# KSM.net
KiCad netlist of a schematic drawn in EAGLE
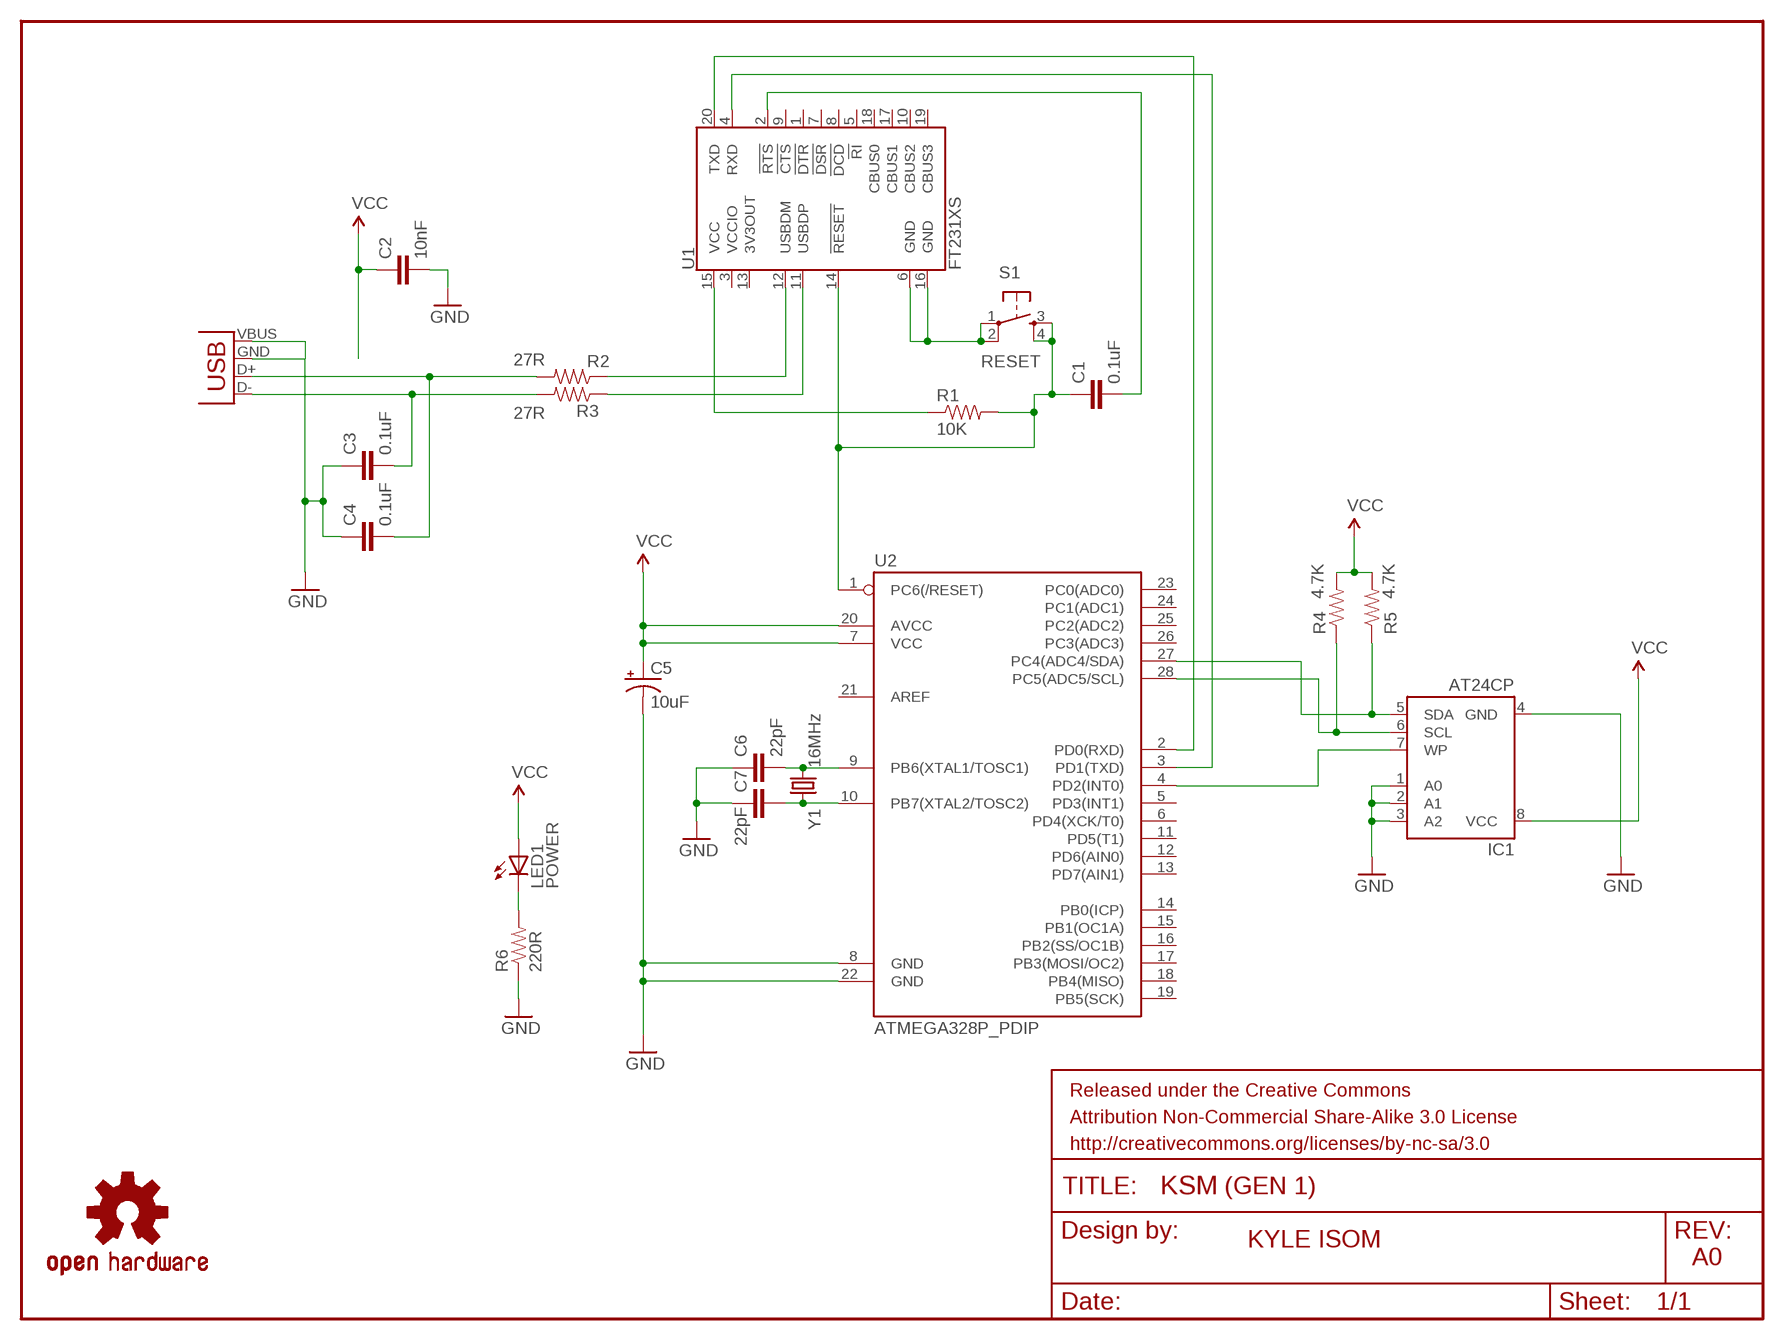
[diagram p0: schematic, sheet 1]

(export (version "E")
  (design (tool "Eeschema 10.0.6"))
  (components
    (comp (ref "C1")
      (value "0.1uF")
      (footprint "eagle-import:CAP-PTH-SMALL")
      (libsource (lib "eagle-import") (part "CAPPTH"))
    )
    (comp (ref "C2")
      (value "10nF")
      (footprint "eagle-import:CAP-PTH-SMALL")
      (libsource (lib "eagle-import") (part "CAPPTH"))
    )
    (comp (ref "C3")
      (value "0.1uF")
      (footprint "eagle-import:CAP-PTH-SMALL")
      (libsource (lib "eagle-import") (part "CAPPTH"))
    )
    (comp (ref "C4")
      (value "0.1uF")
      (footprint "eagle-import:CAP-PTH-SMALL")
      (libsource (lib "eagle-import") (part "CAPPTH"))
    )
    (comp (ref "C5")
      (value "10uF")
      (footprint "eagle-import:CPOL-RADIAL-10UF-25V")
      (libsource (lib "eagle-import") (part "CAP_POLPTH2"))
    )
    (comp (ref "C6")
      (value "22pF")
      (footprint "eagle-import:CAP-PTH-SMALL")
      (libsource (lib "eagle-import") (part "CAPPTH"))
    )
    (comp (ref "C7")
      (value "22pF")
      (footprint "eagle-import:CAP-PTH-SMALL")
      (libsource (lib "eagle-import") (part "CAPPTH"))
    )
    (comp (ref "FRAME1")
      (value "FRAME-LETTER")
      (footprint "eagle-import:CREATIVE_COMMONS")
      (libsource (lib "eagle-import") (part "FRAME-LETTER"))
    )
    (comp (ref "IC1")
      (value "AT24CP")
      (footprint "eagle-import:DIL08")
      (fields (field (name "MPN") "AT24C1024BW-SH-B"))
      (libsource (lib "eagle-import") (part "AT24CP"))
    )
    (comp (ref "JP1")
      (value "USB-A-H")
      (footprint "eagle-import:USB-A-H")
      (libsource (lib "eagle-import") (part "USB-A-H"))
    )
    (comp (ref "LED1")
      (value "POWER")
      (footprint "eagle-import:LED3MM")
      (libsource (lib "eagle-import") (part "LED3MM"))
    )
    (comp (ref "LOGO1")
      (value "OSHW-LOGOL")
      (footprint "eagle-import:OSHW-LOGO-L")
      (libsource (lib "eagle-import") (part "OSHW-LOGOL"))
    )
    (comp (ref "R1")
      (value "10K")
      (footprint "eagle-import:AXIAL-0.4")
      (libsource (lib "eagle-import") (part "RESISTORPTH-1/4W"))
    )
    (comp (ref "R2")
      (value "27R")
      (footprint "eagle-import:AXIAL-0.4")
      (libsource (lib "eagle-import") (part "RESISTORPTH-1/4W"))
    )
    (comp (ref "R3")
      (value "27R")
      (footprint "eagle-import:AXIAL-0.4")
      (libsource (lib "eagle-import") (part "RESISTORPTH-1/4W"))
    )
    (comp (ref "R4")
      (value "4.7K")
      (footprint "eagle-import:AXIAL-0.4")
      (libsource (lib "eagle-import") (part "RESISTORPTH-1/4W"))
    )
    (comp (ref "R5")
      (value "4.7K")
      (footprint "eagle-import:AXIAL-0.4")
      (libsource (lib "eagle-import") (part "RESISTORPTH-1/4W"))
    )
    (comp (ref "R6")
      (value "220R")
      (footprint "eagle-import:AXIAL-0.4")
      (libsource (lib "eagle-import") (part "RESISTORPTH-1/4W"))
    )
    (comp (ref "S1")
      (value "RESET")
      (footprint "eagle-import:TACTILE-PTH")
      (libsource (lib "eagle-import") (part "TAC_SWITCHPTH"))
    )
    (comp (ref "U1")
      (value "FT231XS")
      (footprint "eagle-import:SSOP20_L")
      (libsource (lib "eagle-import") (part "FT231XS"))
    )
    (comp (ref "U2")
      (value "ATMEGA328P_PDIP")
      (footprint "eagle-import:DIL28-3")
      (libsource (lib "eagle-import") (part "ATMEGA328P_PDIP"))
    )
    (comp (ref "Y1")
      (value "16MHz")
      (footprint "eagle-import:HC49US")
      (libsource (lib "eagle-import") (part "CRYSTALHC49US"))
    )
  )
  (nets
    (net (code "1") (name "GND") (class "Default")
      (node (ref "C2") (pin "2") (pinfunction "2_2") (pintype "passive"))
      (node (ref "C3") (pin "1") (pinfunction "1_1") (pintype "passive"))
      (node (ref "C4") (pin "1") (pinfunction "1_1") (pintype "passive"))
      (node (ref "C5") (pin "2") (pinfunction "-_2") (pintype "passive"))
      (node (ref "C6") (pin "1") (pinfunction "1_1") (pintype "passive"))
      (node (ref "C7") (pin "1") (pinfunction "1_1") (pintype "passive"))
      (node (ref "IC1") (pin "1") (pinfunction "A0_1") (pintype "input"))
      (node (ref "IC1") (pin "2") (pinfunction "A1_2") (pintype "input"))
      (node (ref "IC1") (pin "3") (pinfunction "A2_3") (pintype "input"))
      (node (ref "IC1") (pin "4") (pinfunction "GND_4") (pintype "power_in"))
      (node (ref "JP1") (pin "GND") (pinfunction "VBUS_GND") (pintype "bidirectional"))
      (node (ref "JP1") (pin "VBUS") (pinfunction "GND_VBUS") (pintype "bidirectional"))
      (node (ref "R6") (pin "P$1") (pinfunction "1_P$1") (pintype "passive"))
      (node (ref "U2") (pin "22") (pinfunction "GND_22") (pintype "bidirectional"))
      (node (ref "U2") (pin "8") (pinfunction "GND_8") (pintype "bidirectional"))
    )
    (net (code "2") (name "Net-(IC1-SCL)") (class "Default")
      (node (ref "IC1") (pin "6") (pinfunction "SCL_6") (pintype "bidirectional"))
      (node (ref "R4") (pin "P$1") (pinfunction "1_P$1") (pintype "passive"))
      (node (ref "U2") (pin "28") (pinfunction "PC5(ADC5/SCL)_28") (pintype "bidirectional"))
    )
    (net (code "3") (name "Net-(IC1-SDA)") (class "Default")
      (node (ref "IC1") (pin "5") (pinfunction "SDA_5") (pintype "bidirectional"))
      (node (ref "R5") (pin "P$1") (pinfunction "1_P$1") (pintype "passive"))
      (node (ref "U2") (pin "27") (pinfunction "PC4(ADC4/SDA)_27") (pintype "bidirectional"))
    )
    (net (code "4") (name "Net-(IC1-WP)") (class "Default")
      (node (ref "IC1") (pin "7") (pinfunction "WP_7") (pintype "input"))
      (node (ref "U2") (pin "4") (pinfunction "PD2(INT0)_4") (pintype "bidirectional"))
    )
    (net (code "5") (name "Net-(JP1-D+)") (class "Default")
      (node (ref "C3") (pin "2") (pinfunction "2_2") (pintype "passive"))
      (node (ref "JP1") (pin "D-") (pinfunction "D+_D-") (pintype "bidirectional"))
      (node (ref "R3") (pin "P$2") (pinfunction "2_P$2") (pintype "passive"))
    )
    (net (code "6") (name "Net-(JP1-D-)") (class "Default")
      (node (ref "C4") (pin "2") (pinfunction "2_2") (pintype "passive"))
      (node (ref "JP1") (pin "D+") (pinfunction "D-_D+") (pintype "bidirectional"))
      (node (ref "R2") (pin "P$2") (pinfunction "2_P$2") (pintype "passive"))
    )
    (net (code "7") (name "Net-(LED1-C)") (class "Default")
      (node (ref "LED1") (pin "K") (pinfunction "C_K") (pintype "passive"))
      (node (ref "R6") (pin "P$2") (pinfunction "2_P$2") (pintype "passive"))
    )
    (net (code "8") (name "Net-(R1-1)") (class "Default")
      (node (ref "R1") (pin "P$1") (pinfunction "1_P$1") (pintype "passive"))
      (node (ref "U1") (pin "15") (pinfunction "VCC_15") (pintype "bidirectional"))
    )
    (net (code "9") (name "Net-(R1-2)") (class "Default")
      (node (ref "C1") (pin "1") (pinfunction "1_1") (pintype "passive"))
      (node (ref "R1") (pin "P$2") (pinfunction "2_P$2") (pintype "passive"))
      (node (ref "S1") (pin "3") (pinfunction "3_3") (pintype "passive"))
      (node (ref "S1") (pin "4") (pinfunction "4_4") (pintype "passive"))
      (node (ref "U1") (pin "14") (pinfunction "~{RESET}_14") (pintype "bidirectional"))
      (node (ref "U2") (pin "1") (pinfunction "PC6(/RESET)_1") (pintype "bidirectional"))
    )
    (net (code "10") (name "Net-(R2-1)") (class "Default")
      (node (ref "R2") (pin "P$1") (pinfunction "1_P$1") (pintype "passive"))
      (node (ref "U1") (pin "12") (pinfunction "USBDM_12") (pintype "bidirectional"))
    )
    (net (code "11") (name "Net-(R3-1)") (class "Default")
      (node (ref "R3") (pin "P$1") (pinfunction "1_P$1") (pintype "passive"))
      (node (ref "U1") (pin "11") (pinfunction "USBDP_11") (pintype "bidirectional"))
    )
    (net (code "12") (name "Net-(S1-Pad1)") (class "Default")
      (node (ref "S1") (pin "1") (pinfunction "1_1") (pintype "passive"))
      (node (ref "S1") (pin "2") (pinfunction "2_2") (pintype "passive"))
      (node (ref "U1") (pin "16") (pinfunction "GND_16") (pintype "bidirectional"))
      (node (ref "U1") (pin "6") (pinfunction "GND_6") (pintype "bidirectional"))
    )
    (net (code "13") (name "Net-(U1-RXD)") (class "Default")
      (node (ref "U1") (pin "4") (pinfunction "RXD_4") (pintype "bidirectional"))
      (node (ref "U2") (pin "3") (pinfunction "PD1(TXD)_3") (pintype "bidirectional"))
    )
    (net (code "14") (name "Net-(U1-TXD)") (class "Default")
      (node (ref "U1") (pin "20") (pinfunction "TXD_20") (pintype "bidirectional"))
      (node (ref "U2") (pin "2") (pinfunction "PD0(RXD)_2") (pintype "bidirectional"))
    )
    (net (code "15") (name "Net-(U1-~{RTS})") (class "Default")
      (node (ref "C1") (pin "2") (pinfunction "2_2") (pintype "passive"))
      (node (ref "U1") (pin "2") (pinfunction "~{RTS}_2") (pintype "bidirectional"))
    )
    (net (code "16") (name "Net-(U2-PB6(XTAL1{slash}TOSC1))") (class "Default")
      (node (ref "C6") (pin "2") (pinfunction "2_2") (pintype "passive"))
      (node (ref "U2") (pin "9") (pinfunction "PB6(XTAL1/TOSC1)_9") (pintype "bidirectional"))
      (node (ref "Y1") (pin "2") (pinfunction "2_2") (pintype "passive"))
    )
    (net (code "17") (name "Net-(U2-PB7(XTAL2{slash}TOSC2))") (class "Default")
      (node (ref "C7") (pin "2") (pinfunction "2_2") (pintype "passive"))
      (node (ref "U2") (pin "10") (pinfunction "PB7(XTAL2/TOSC2)_10") (pintype "bidirectional"))
      (node (ref "Y1") (pin "1") (pinfunction "1_1") (pintype "passive"))
    )
    (net (code "18") (name "VCC") (class "Default")
      (node (ref "C2") (pin "1") (pinfunction "1_1") (pintype "passive"))
      (node (ref "C5") (pin "1") (pinfunction "+_1") (pintype "passive"))
      (node (ref "IC1") (pin "8") (pinfunction "VCC_8") (pintype "power_in"))
      (node (ref "LED1") (pin "A") (pinfunction "A_A") (pintype "passive"))
      (node (ref "R4") (pin "P$2") (pinfunction "2_P$2") (pintype "passive"))
      (node (ref "R5") (pin "P$2") (pinfunction "2_P$2") (pintype "passive"))
      (node (ref "U2") (pin "20") (pinfunction "AVCC_20") (pintype "bidirectional"))
      (node (ref "U2") (pin "7") (pinfunction "VCC_7") (pintype "bidirectional"))
    )
    (net (code "19") (name "unconnected-(U1-3V3OUT-Pad13)") (class "Default")
      (node (ref "U1") (pin "13") (pinfunction "3V3OUT_13") (pintype "bidirectional"))
    )
    (net (code "20") (name "unconnected-(U1-CBUS0-Pad18)") (class "Default")
      (node (ref "U1") (pin "18") (pinfunction "CBUS0_18") (pintype "bidirectional"))
    )
    (net (code "21") (name "unconnected-(U1-CBUS1-Pad17)") (class "Default")
      (node (ref "U1") (pin "17") (pinfunction "CBUS1_17") (pintype "bidirectional"))
    )
    (net (code "22") (name "unconnected-(U1-CBUS2-Pad10)") (class "Default")
      (node (ref "U1") (pin "10") (pinfunction "CBUS2_10") (pintype "bidirectional"))
    )
    (net (code "23") (name "unconnected-(U1-CBUS3-Pad19)") (class "Default")
      (node (ref "U1") (pin "19") (pinfunction "CBUS3_19") (pintype "bidirectional"))
    )
    (net (code "24") (name "unconnected-(U1-VCCIO-Pad3)") (class "Default")
      (node (ref "U1") (pin "3") (pinfunction "VCCIO_3") (pintype "bidirectional"))
    )
    (net (code "25") (name "unconnected-(U1-~{CTS}-Pad9)") (class "Default")
      (node (ref "U1") (pin "9") (pinfunction "~{CTS}_9") (pintype "bidirectional"))
    )
    (net (code "26") (name "unconnected-(U1-~{DCD}-Pad8)") (class "Default")
      (node (ref "U1") (pin "8") (pinfunction "~{DCD}_8") (pintype "bidirectional"))
    )
    (net (code "27") (name "unconnected-(U1-~{DSR}-Pad7)") (class "Default")
      (node (ref "U1") (pin "7") (pinfunction "~{DSR}_7") (pintype "bidirectional"))
    )
    (net (code "28") (name "unconnected-(U1-~{DTR}-Pad1)") (class "Default")
      (node (ref "U1") (pin "1") (pinfunction "~{DTR}_1") (pintype "bidirectional"))
    )
    (net (code "29") (name "unconnected-(U1-~{RI}-Pad5)") (class "Default")
      (node (ref "U1") (pin "5") (pinfunction "~{RI}_5") (pintype "bidirectional"))
    )
    (net (code "30") (name "unconnected-(U2-AREF-Pad21)") (class "Default")
      (node (ref "U2") (pin "21") (pinfunction "AREF_21") (pintype "bidirectional"))
    )
    (net (code "31") (name "unconnected-(U2-PB0(ICP)-Pad14)") (class "Default")
      (node (ref "U2") (pin "14") (pinfunction "PB0(ICP)_14") (pintype "bidirectional"))
    )
    (net (code "32") (name "unconnected-(U2-PB1(OC1A)-Pad15)") (class "Default")
      (node (ref "U2") (pin "15") (pinfunction "PB1(OC1A)_15") (pintype "bidirectional"))
    )
    (net (code "33") (name "unconnected-(U2-PB2(SS{slash}OC1B)-Pad16)") (class "Default")
      (node (ref "U2") (pin "16") (pinfunction "PB2(SS/OC1B)_16") (pintype "bidirectional"))
    )
    (net (code "34") (name "unconnected-(U2-PB3(MOSI{slash}OC2)-Pad17)") (class "Default")
      (node (ref "U2") (pin "17") (pinfunction "PB3(MOSI/OC2)_17") (pintype "bidirectional"))
    )
    (net (code "35") (name "unconnected-(U2-PB4(MISO)-Pad18)") (class "Default")
      (node (ref "U2") (pin "18") (pinfunction "PB4(MISO)_18") (pintype "bidirectional"))
    )
    (net (code "36") (name "unconnected-(U2-PB5(SCK)-Pad19)") (class "Default")
      (node (ref "U2") (pin "19") (pinfunction "PB5(SCK)_19") (pintype "bidirectional"))
    )
    (net (code "37") (name "unconnected-(U2-PC0(ADC0)-Pad23)") (class "Default")
      (node (ref "U2") (pin "23") (pinfunction "PC0(ADC0)_23") (pintype "bidirectional"))
    )
    (net (code "38") (name "unconnected-(U2-PC1(ADC1)-Pad24)") (class "Default")
      (node (ref "U2") (pin "24") (pinfunction "PC1(ADC1)_24") (pintype "bidirectional"))
    )
    (net (code "39") (name "unconnected-(U2-PC2(ADC2)-Pad25)") (class "Default")
      (node (ref "U2") (pin "25") (pinfunction "PC2(ADC2)_25") (pintype "bidirectional"))
    )
    (net (code "40") (name "unconnected-(U2-PC3(ADC3)-Pad26)") (class "Default")
      (node (ref "U2") (pin "26") (pinfunction "PC3(ADC3)_26") (pintype "bidirectional"))
    )
    (net (code "41") (name "unconnected-(U2-PD3(INT1)-Pad5)") (class "Default")
      (node (ref "U2") (pin "5") (pinfunction "PD3(INT1)_5") (pintype "bidirectional"))
    )
    (net (code "42") (name "unconnected-(U2-PD4(XCK{slash}T0)-Pad6)") (class "Default")
      (node (ref "U2") (pin "6") (pinfunction "PD4(XCK/T0)_6") (pintype "bidirectional"))
    )
    (net (code "43") (name "unconnected-(U2-PD5(T1)-Pad11)") (class "Default")
      (node (ref "U2") (pin "11") (pinfunction "PD5(T1)_11") (pintype "bidirectional"))
    )
    (net (code "44") (name "unconnected-(U2-PD6(AIN0)-Pad12)") (class "Default")
      (node (ref "U2") (pin "12") (pinfunction "PD6(AIN0)_12") (pintype "bidirectional"))
    )
    (net (code "45") (name "unconnected-(U2-PD7(AIN1)-Pad13)") (class "Default")
      (node (ref "U2") (pin "13") (pinfunction "PD7(AIN1)_13") (pintype "bidirectional"))
    )
  )
)
